# USB-C.net
KiCad netlist of a schematic drawn in Altium Designer
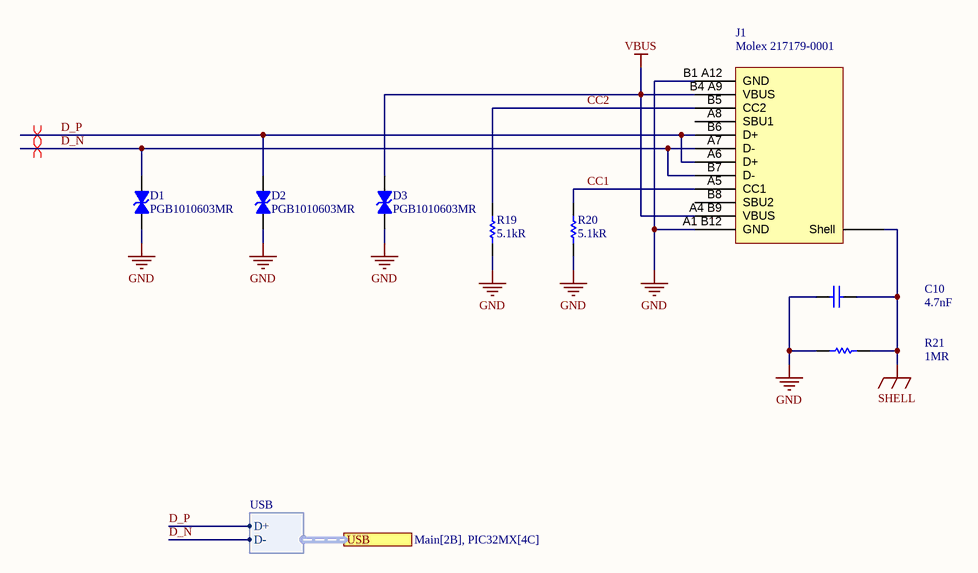
[diagram p0: USB-C.SchDoc]

(export (version "E")
  (design (tool "Eeschema 10.0.6"))
  (components
    (comp (ref "C10")
      (value "4.7nF")
      (footprint "Capacitor 0603")
      (libsource (lib "x-io") (part "Capacitor"))
    )
    (comp (ref "D1")
      (value "PGB1010603MR")
      (footprint "Diode TVS 0603")
      (libsource (lib "x-io") (part "Diode TVS"))
    )
    (comp (ref "D2")
      (value "PGB1010603MR")
      (footprint "Diode TVS 0603")
      (libsource (lib "x-io") (part "Diode TVS"))
    )
    (comp (ref "D3")
      (value "PGB1010603MR")
      (footprint "Diode TVS 0603")
      (libsource (lib "x-io") (part "Diode TVS"))
    )
    (comp (ref "J1")
      (value "Molex 217179-0001")
      (footprint "Molex 217179-0001")
      (libsource (lib "x-io") (part "USB-C Receptacle (16 Pin)"))
    )
    (comp (ref "R19") (value "5.1kR") (footprint "Resistor 0603") (libsource (lib "x-io") (part "Resistor")))
    (comp (ref "R20") (value "5.1kR") (footprint "Resistor 0603") (libsource (lib "x-io") (part "Resistor")))
    (comp (ref "R21") (value "1MR") (footprint "Resistor 0603") (libsource (lib "x-io") (part "Resistor")))
  )
  (nets
    (net (code "2") (name "/CC1") (class "Default")
      (node (ref "J1") (pin "A5") (pinfunction "CC1_A5") (pintype "passive"))
      (node (ref "R20") (pin "2") (pinfunction "2_2") (pintype "passive"))
    )
    (net (code "3") (name "/CC2") (class "Default")
      (node (ref "J1") (pin "B5") (pinfunction "CC2_B5") (pintype "passive"))
      (node (ref "R19") (pin "2") (pinfunction "2_2") (pintype "passive"))
    )
    (net (code "4") (name "/D_N") (class "Default")
      (node (ref "D1") (pin "1") (pinfunction "*_1") (pintype "passive"))
      (node (ref "J1") (pin "A7") (pinfunction "D-_A7") (pintype "passive"))
      (node (ref "J1") (pin "B7") (pinfunction "D-_B7") (pintype "passive"))
    )
    (net (code "5") (name "/D_P") (class "Default")
      (node (ref "D2") (pin "1") (pinfunction "*_1") (pintype "passive"))
      (node (ref "J1") (pin "A6") (pinfunction "D+_A6") (pintype "passive"))
      (node (ref "J1") (pin "B6") (pinfunction "D+_B6") (pintype "passive"))
    )
    (net (code "7") (name "GND") (class "Default")
      (node (ref "C10") (pin "1") (pinfunction "1_1") (pintype "passive"))
      (node (ref "D1") (pin "2") (pinfunction "*_2") (pintype "passive"))
      (node (ref "D2") (pin "2") (pinfunction "*_2") (pintype "passive"))
      (node (ref "D3") (pin "2") (pinfunction "*_2") (pintype "passive"))
      (node (ref "J1") (pin "A1_B12") (pinfunction "GND_A1_B12") (pintype "passive"))
      (node (ref "J1") (pin "B1_A12") (pinfunction "GND_B1_A12") (pintype "passive"))
      (node (ref "R19") (pin "1") (pinfunction "1_1") (pintype "passive"))
      (node (ref "R20") (pin "1") (pinfunction "1_1") (pintype "passive"))
      (node (ref "R21") (pin "2") (pinfunction "2_2") (pintype "passive"))
    )
    (net (code "8") (name "SHELL") (class "Default")
      (node (ref "C10") (pin "2") (pinfunction "2_2") (pintype "passive"))
      (node (ref "J1") (pin "Shell") (pinfunction "Shell_Shell") (pintype "passive"))
      (node (ref "R21") (pin "1") (pinfunction "1_1") (pintype "passive"))
    )
    (net (code "9") (name "VBUS") (class "Default")
      (node (ref "D3") (pin "1") (pinfunction "*_1") (pintype "passive"))
      (node (ref "J1") (pin "A4_B9") (pinfunction "VBUS_A4_B9") (pintype "passive"))
      (node (ref "J1") (pin "B4_A9") (pinfunction "VBUS_B4_A9") (pintype "passive"))
    )
    (net (code "10") (name "unconnected-(J1-SBU1-PadA8)") (class "Default")
      (node (ref "J1") (pin "A8") (pinfunction "SBU1_A8") (pintype "passive"))
    )
    (net (code "11") (name "unconnected-(J1-SBU2-PadB8)") (class "Default")
      (node (ref "J1") (pin "B8") (pinfunction "SBU2_B8") (pintype "passive"))
    )
  )
)
